# Power.net
KiCad netlist of a schematic drawn in Altium Designer
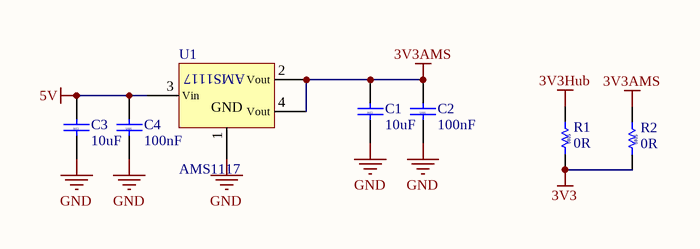
[diagram p0: Power.SchDoc]

(export (version "E")
  (design (tool "Eeschema 10.0.6"))
  (components
    (comp (ref "C1")
      (value "10uF")
      (footprint "Res 1206")
      (libsource (lib "Full lib F.kh-V2") (part "CAP 1206"))
    )
    (comp (ref "C2")
      (value "100nF")
      (footprint "RES 0805")
      (libsource (lib "Full lib F.kh-V2") (part "CAP 0805"))
    )
    (comp (ref "C3")
      (value "10uF")
      (footprint "Res 1206")
      (libsource (lib "Full lib F.kh-V2") (part "CAP 1206"))
    )
    (comp (ref "C4")
      (value "100nF")
      (footprint "RES 0805")
      (libsource (lib "Full lib F.kh-V2") (part "CAP 0805"))
    )
    (comp (ref "R1")
      (value "0R")
      (footprint "RES 0805")
      (libsource (lib "Full lib F.kh-V2") (part "RES 0805"))
    )
    (comp (ref "R2")
      (value "0R")
      (footprint "RES 0805")
      (libsource (lib "Full lib F.kh-V2") (part "RES 0805"))
    )
    (comp (ref "U1")
      (value "AMS1117")
      (footprint "SOT-223")
      (description "Regulators")
      (libsource (lib "Full lib F.kh-V2") (part "AMS1117"))
    )
  )
  (nets
    (net (code "1") (name "3V3") (class "Default")
      (node (ref "R1") (pin "2") (pinfunction "2_2") (pintype "passive"))
      (node (ref "R2") (pin "2") (pinfunction "2_2") (pintype "passive"))
    )
    (net (code "2") (name "3V3AMS") (class "Default")
      (node (ref "C1") (pin "2") (pinfunction "2_2") (pintype "passive"))
      (node (ref "C2") (pin "2") (pinfunction "2_2") (pintype "passive"))
      (node (ref "R2") (pin "1") (pinfunction "1_1") (pintype "passive"))
      (node (ref "U1") (pin "2") (pinfunction "Vout_2") (pintype "passive"))
      (node (ref "U1") (pin "4") (pinfunction "Vout_4") (pintype "passive"))
    )
    (net (code "3") (name "3V3Hub") (class "Default")
      (node (ref "R1") (pin "1") (pinfunction "1_1") (pintype "passive"))
    )
    (net (code "4") (name "5V") (class "Default")
      (node (ref "C3") (pin "2") (pinfunction "2_2") (pintype "passive"))
      (node (ref "C4") (pin "2") (pinfunction "2_2") (pintype "passive"))
      (node (ref "U1") (pin "3") (pinfunction "Vin_3") (pintype "passive"))
    )
    (net (code "5") (name "GND") (class "Default")
      (node (ref "C1") (pin "1") (pinfunction "1_1") (pintype "passive"))
      (node (ref "C2") (pin "1") (pinfunction "1_1") (pintype "passive"))
      (node (ref "C3") (pin "1") (pinfunction "1_1") (pintype "passive"))
      (node (ref "C4") (pin "1") (pinfunction "1_1") (pintype "passive"))
      (node (ref "U1") (pin "1") (pinfunction "GND_1") (pintype "passive"))
    )
  )
)
